# SCIENCE_LED_BOARD.net
KiCad netlist of a schematic drawn in Altium Designer
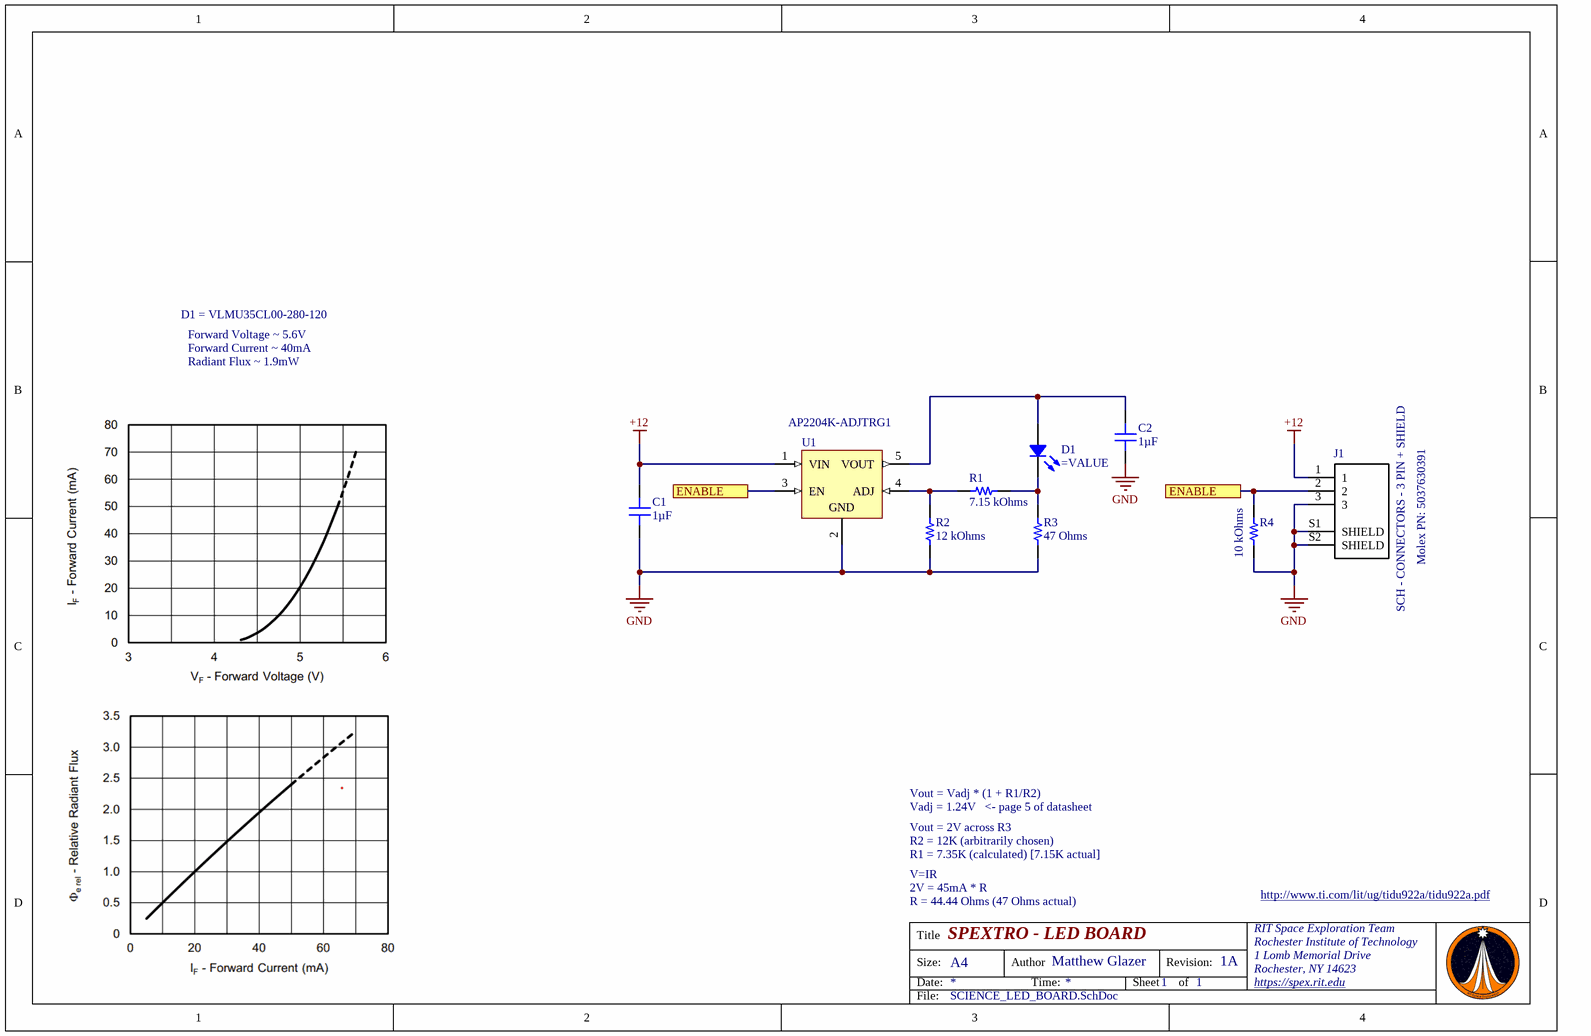
[diagram p0: SCIENCE_LED_BOARD.SchDoc]

(export (version "E")
  (design (tool "Eeschema 10.0.6"))
  (components
    (comp (ref "C1")
      (value "1µF")
      (footprint "CAP 0603_1608")
      (description "CAP CER 1UF 25V X5R 0603")
      (fields (field (name "PART NUMBER") "CC0603KRX5R8BB105") (field (name "MANUFACTURER") "Yageo"))
      (libsource (lib "Celestial Altium Library - altium_library") (part "Capacitor"))
    )
    (comp (ref "C2")
      (value "1µF")
      (footprint "CAP 0603_1608")
      (description "CAP CER 1UF 25V X5R 0603")
      (fields (field (name "PART NUMBER") "CC0603KRX5R8BB105") (field (name "MANUFACTURER") "Yageo"))
      (libsource (lib "Celestial Altium Library - altium_library") (part "Capacitor"))
    )
    (comp (ref "D1")
      (value "~")
      (footprint "PCB - LED - VISHAY 1414_3535 UV")
      (description "Chip LED")
      (libsource (lib "ScienceLEDLibrary") (part "LED"))
    )
    (comp (ref "J1")
      (value "SCH - CONNECTORS - 3 PIN + SHIELD")
      (footprint "PCB - CONNECTOR - MOLEX - PICO-LOCK 5037630391")
      (description "Connector Header Surface Mount, Right Angle 4 position 0.039 _1.00mm_")
      (fields (field (name "MF") "Molex") (field (name "MP") "5037630391"))
      (libsource (lib "ScienceLEDLibrary") (part "SCH - CONNECTORS - 3 PIN + SHIELD"))
    )
    (comp (ref "R1")
      (value "7.15 kOhms")
      (footprint "RES 0603_1608")
      (description "RES 7.15K OHM 1% 1/10W 0603")
      (fields
        (field (name "PART NUMBER") "RMCF0603FT7K15")
        (field (name "MANUFACTURER") "Stackpole Electronics Inc")
      )
      (libsource (lib "Celestial Altium Library - altium_library") (part "Resistor"))
    )
    (comp (ref "R2")
      (value "12 kOhms")
      (footprint "RES 0603_1608")
      (description "RES 12K OHM 1% 1/10W 0603")
      (fields
        (field (name "PART NUMBER") "RMCF0603FT12K0")
        (field (name "MANUFACTURER") "Stackpole Electronics Inc")
      )
      (libsource (lib "Celestial Altium Library - altium_library") (part "Resistor"))
    )
    (comp (ref "R3")
      (value "47 Ohms")
      (footprint "RES 0603_1608")
      (description "RES 47 OHM 1% 1/10W 0603")
      (fields
        (field (name "PART NUMBER") "RMCF0603FT47R0")
        (field (name "MANUFACTURER") "Stackpole Electronics Inc")
      )
      (libsource (lib "Celestial Altium Library - altium_library") (part "Resistor"))
    )
    (comp (ref "R4")
      (value "10 kOhms")
      (footprint "RES 0603_1608")
      (description "RES 10K OHM 1% 1/10W 0603")
      (fields
        (field (name "PART NUMBER") "RMCF0603FT10K0")
        (field (name "MANUFACTURER") "Stackpole Electronics Inc")
      )
      (libsource (lib "Celestial Altium Library - altium_library") (part "Resistor"))
    )
    (comp (ref "U1")
      (value "AP2204K-ADJTRG1")
      (footprint "DIOD-SOT23-5_V")
      (fields (field (name "MANUFACTURER") "DiodesIncorporated"))
      (libsource (lib "Altium Content Vault") (part "DIOD-AP2204-ADJ-SOT23-5"))
    )
  )
  (nets
    (net (code "1") (name "+12") (class "Default")
      (node (ref "C1") (pin "2") (pinfunction "2_2") (pintype "passive"))
      (node (ref "J1") (pin "1") (pinfunction "1_1") (pintype "passive"))
      (node (ref "U1") (pin "1") (pinfunction "VIN_1") (pintype "input"))
    )
    (net (code "2") (name "/ENABLE") (class "Default")
      (node (ref "J1") (pin "2") (pinfunction "2_2") (pintype "passive"))
      (node (ref "R4") (pin "2") (pinfunction "2_2") (pintype "passive"))
      (node (ref "U1") (pin "3") (pinfunction "EN_3") (pintype "input"))
    )
    (net (code "3") (name "GND") (class "Default")
      (node (ref "C1") (pin "1") (pinfunction "1_1") (pintype "passive"))
      (node (ref "C2") (pin "1") (pinfunction "1_1") (pintype "passive"))
      (node (ref "J1") (pin "3") (pinfunction "3_3") (pintype "passive"))
      (node (ref "J1") (pin "S1") (pinfunction "SHIELD_S1") (pintype "passive"))
      (node (ref "J1") (pin "S2") (pinfunction "SHIELD_S2") (pintype "passive"))
      (node (ref "R2") (pin "1") (pinfunction "1_1") (pintype "passive"))
      (node (ref "R3") (pin "1") (pinfunction "1_1") (pintype "passive"))
      (node (ref "R4") (pin "1") (pinfunction "1_1") (pintype "passive"))
      (node (ref "U1") (pin "2") (pinfunction "GND_2") (pintype "power_in"))
    )
    (net (code "4") (name "Net-(D1-Pad2)") (class "Default")
      (node (ref "D1") (pin "2") (pinfunction "2_2") (pintype "passive"))
      (node (ref "R1") (pin "2") (pinfunction "2_2") (pintype "passive"))
      (node (ref "R3") (pin "2") (pinfunction "2_2") (pintype "passive"))
    )
    (net (code "5") (name "Net-(U1-ADJ)") (class "Default")
      (node (ref "R1") (pin "1") (pinfunction "1_1") (pintype "passive"))
      (node (ref "R2") (pin "2") (pinfunction "2_2") (pintype "passive"))
      (node (ref "U1") (pin "4") (pinfunction "ADJ_4") (pintype "input"))
    )
    (net (code "6") (name "Net-(U1-VOUT)") (class "Default")
      (node (ref "C2") (pin "2") (pinfunction "2_2") (pintype "passive"))
      (node (ref "D1") (pin "1") (pinfunction "1_1") (pintype "passive"))
      (node (ref "U1") (pin "5") (pinfunction "VOUT_5") (pintype "output"))
    )
  )
)
